# PIC18F2550_BOARD.net
KiCad netlist of a schematic drawn in EAGLE
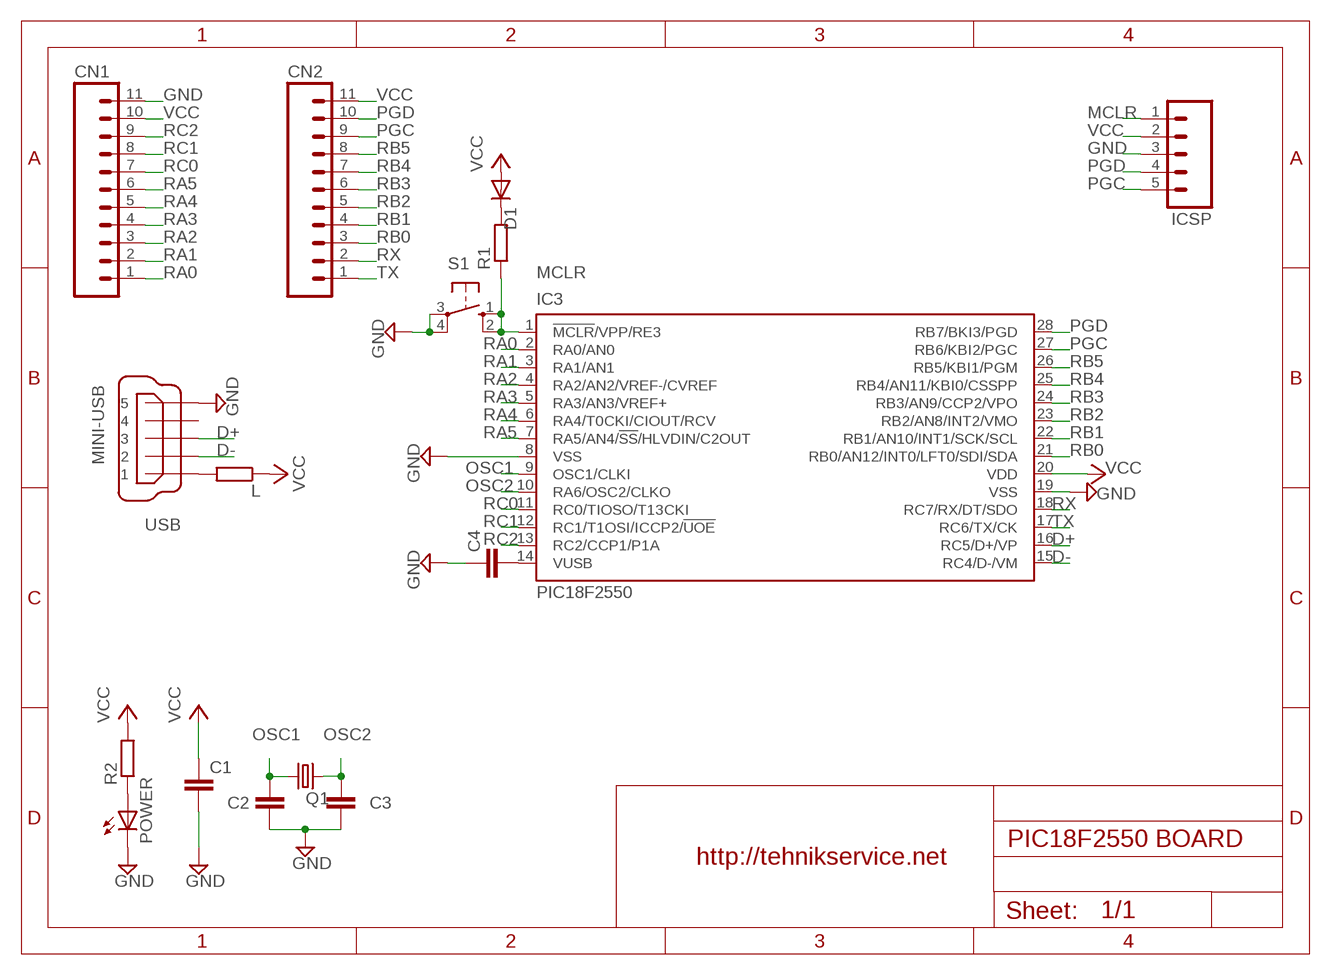
[diagram p0: schematic, sheet 1]

(export (version "E")
  (design (tool "Eeschema 10.0.6"))
  (components
    (comp (ref "C1")
      (value "C-EUC0402")
      (footprint "eagle-import:C0402")
      (libsource (lib "eagle-import") (part "C-EUC0402"))
    )
    (comp (ref "C2")
      (value "C-EUC0402")
      (footprint "eagle-import:C0402")
      (libsource (lib "eagle-import") (part "C-EUC0402"))
    )
    (comp (ref "C3")
      (value "C-EUC0402")
      (footprint "eagle-import:C0402")
      (libsource (lib "eagle-import") (part "C-EUC0402"))
    )
    (comp (ref "C4")
      (value "C-EUC0402")
      (footprint "eagle-import:C0402")
      (libsource (lib "eagle-import") (part "C-EUC0402"))
    )
    (comp (ref "CN1")
      (value "M11")
      (footprint "eagle-import:11P")
      (libsource (lib "eagle-import") (part "M11"))
    )
    (comp (ref "CN2")
      (value "M11")
      (footprint "eagle-import:11P")
      (libsource (lib "eagle-import") (part "M11"))
    )
    (comp (ref "D1")
      (value "DIODE-DO214AC")
      (footprint "eagle-import:DO214AC")
      (libsource (lib "eagle-import") (part "DIODE-DO214AC"))
    )
    (comp (ref "IC3")
      (value "PIC18F2550")
      (footprint "eagle-import:SO28W")
      (fields (field (name "MF") "MICROCHIP") (field (name "MPN") "PIC18F2550-I/SO"))
      (libsource (lib "eagle-import") (part "PIC18F2_28W550"))
    )
    (comp (ref "ICSP")
      (value "M05")
      (footprint "eagle-import:05P")
      (libsource (lib "eagle-import") (part "M05"))
    )
    (comp (ref "L")
      (value "R-EU_R0402")
      (footprint "eagle-import:R0402")
      (libsource (lib "eagle-import") (part "R-EU_R0402"))
    )
    (comp (ref "POWER")
      (value "LEDCHIP-LED0805")
      (footprint "eagle-import:CHIP-LED0805")
      (libsource (lib "eagle-import") (part "LEDCHIP-LED0805"))
    )
    (comp (ref "Q1")
      (value "CRYSTALHC49S")
      (footprint "eagle-import:HC49_S")
      (libsource (lib "eagle-import") (part "CRYSTALHC49S"))
    )
    (comp (ref "R1")
      (value "R-EU_R0402")
      (footprint "eagle-import:R0402")
      (libsource (lib "eagle-import") (part "R-EU_R0402"))
    )
    (comp (ref "R2")
      (value "R-EU_R0402")
      (footprint "eagle-import:R0402")
      (libsource (lib "eagle-import") (part "R-EU_R0402"))
    )
    (comp (ref "S1")
      (value "10-XX")
      (footprint "eagle-import:B3F-10XX")
      (fields (field (name "MPN") "B3F-1000"))
      (libsource (lib "eagle-import") (part "10-XX"))
    )
    (comp (ref "USB")
      (value "MINI-USB")
      (footprint "eagle-import:32005-201")
      (libsource (lib "eagle-import") (part "MINI-USB-32005-201"))
    )
  )
  (nets
    (net (code "1") (name "/D+") (class "Default")
      (node (ref "IC3") (pin "16") (pinfunction "RC5/D+/VP_16") (pintype "bidirectional"))
      (node (ref "USB") (pin "3") (pinfunction "3_3") (pintype "passive"))
    )
    (net (code "2") (name "/D-") (class "Default")
      (node (ref "IC3") (pin "15") (pinfunction "RC4/D-/VM_15") (pintype "bidirectional"))
      (node (ref "USB") (pin "2") (pinfunction "2_2") (pintype "passive"))
    )
    (net (code "3") (name "/MCLR") (class "Default")
      (node (ref "IC3") (pin "1") (pinfunction "~{MCLR}/VPP/RE3_1") (pintype "input"))
      (node (ref "ICSP") (pin "1") (pinfunction "1_1") (pintype "passive"))
      (node (ref "R1") (pin "1") (pinfunction "1_1") (pintype "passive"))
      (node (ref "S1") (pin "1") (pinfunction "S_1") (pintype "passive"))
      (node (ref "S1") (pin "2") (pinfunction "S1_2") (pintype "passive"))
    )
    (net (code "4") (name "/OSC1") (class "Default")
      (node (ref "C2") (pin "1") (pinfunction "1_1") (pintype "passive"))
      (node (ref "IC3") (pin "9") (pinfunction "OSC1/CLKI_9") (pintype "input"))
      (node (ref "Q1") (pin "1") (pinfunction "1_1") (pintype "passive"))
    )
    (net (code "5") (name "/OSC2") (class "Default")
      (node (ref "C3") (pin "1") (pinfunction "1_1") (pintype "passive"))
      (node (ref "IC3") (pin "10") (pinfunction "RA6/OSC2/CLKO_10") (pintype "output"))
      (node (ref "Q1") (pin "2") (pinfunction "2_2") (pintype "passive"))
    )
    (net (code "6") (name "/PGC") (class "Default")
      (node (ref "CN2") (pin "9") (pinfunction "9_9") (pintype "passive"))
      (node (ref "IC3") (pin "27") (pinfunction "RB6/KBI2/PGC_27") (pintype "bidirectional"))
      (node (ref "ICSP") (pin "5") (pinfunction "5_5") (pintype "passive"))
    )
    (net (code "7") (name "/PGD") (class "Default")
      (node (ref "CN2") (pin "10") (pinfunction "10_10") (pintype "passive"))
      (node (ref "IC3") (pin "28") (pinfunction "RB7/BKI3/PGD_28") (pintype "bidirectional"))
      (node (ref "ICSP") (pin "4") (pinfunction "4_4") (pintype "passive"))
    )
    (net (code "8") (name "/RA0") (class "Default")
      (node (ref "CN1") (pin "1") (pinfunction "1_1") (pintype "passive"))
      (node (ref "IC3") (pin "2") (pinfunction "RA0/AN0_2") (pintype "bidirectional"))
    )
    (net (code "9") (name "/RA1") (class "Default")
      (node (ref "CN1") (pin "2") (pinfunction "2_2") (pintype "passive"))
      (node (ref "IC3") (pin "3") (pinfunction "RA1/AN1_3") (pintype "bidirectional"))
    )
    (net (code "10") (name "/RA2") (class "Default")
      (node (ref "CN1") (pin "3") (pinfunction "3_3") (pintype "passive"))
      (node (ref "IC3") (pin "4") (pinfunction "RA2/AN2/VREF-/CVREF_4") (pintype "bidirectional"))
    )
    (net (code "11") (name "/RA3") (class "Default")
      (node (ref "CN1") (pin "4") (pinfunction "4_4") (pintype "passive"))
      (node (ref "IC3") (pin "5") (pinfunction "RA3/AN3/VREF+_5") (pintype "bidirectional"))
    )
    (net (code "12") (name "/RA4") (class "Default")
      (node (ref "CN1") (pin "5") (pinfunction "5_5") (pintype "passive"))
      (node (ref "IC3") (pin "6") (pinfunction "RA4/T0CKI/CIOUT/RCV_6") (pintype "bidirectional"))
    )
    (net (code "13") (name "/RA5") (class "Default")
      (node (ref "CN1") (pin "6") (pinfunction "6_6") (pintype "passive"))
      (node (ref "IC3") (pin "7") (pinfunction "RA5/AN4/~{SS}/HLVDIN/C2OUT_7") (pintype "bidirectional"))
    )
    (net (code "14") (name "/RB0") (class "Default")
      (node (ref "CN2") (pin "3") (pinfunction "3_3") (pintype "passive"))
      (node (ref "IC3") (pin "21") (pinfunction "RB0/AN12/INT0/LFT0/SDI/SDA_21") (pintype "bidirectional"))
    )
    (net (code "15") (name "/RB1") (class "Default")
      (node (ref "CN2") (pin "4") (pinfunction "4_4") (pintype "passive"))
      (node (ref "IC3") (pin "22") (pinfunction "RB1/AN10/INT1/SCK/SCL_22") (pintype "bidirectional"))
    )
    (net (code "16") (name "/RB2") (class "Default")
      (node (ref "CN2") (pin "5") (pinfunction "5_5") (pintype "passive"))
      (node (ref "IC3") (pin "23") (pinfunction "RB2/AN8/INT2/VMO_23") (pintype "bidirectional"))
    )
    (net (code "17") (name "/RB3") (class "Default")
      (node (ref "CN2") (pin "6") (pinfunction "6_6") (pintype "passive"))
      (node (ref "IC3") (pin "24") (pinfunction "RB3/AN9/CCP2/VPO_24") (pintype "bidirectional"))
    )
    (net (code "18") (name "/RB4") (class "Default")
      (node (ref "CN2") (pin "7") (pinfunction "7_7") (pintype "passive"))
      (node (ref "IC3") (pin "25") (pinfunction "RB4/AN11/KBI0/CSSPP_25") (pintype "bidirectional"))
    )
    (net (code "19") (name "/RB5") (class "Default")
      (node (ref "CN2") (pin "8") (pinfunction "8_8") (pintype "passive"))
      (node (ref "IC3") (pin "26") (pinfunction "RB5/KBI1/PGM_26") (pintype "bidirectional"))
    )
    (net (code "20") (name "/RC0") (class "Default")
      (node (ref "CN1") (pin "7") (pinfunction "7_7") (pintype "passive"))
      (node (ref "IC3") (pin "11") (pinfunction "RC0/TIOSO/T13CKI_11") (pintype "bidirectional"))
    )
    (net (code "21") (name "/RC1") (class "Default")
      (node (ref "CN1") (pin "8") (pinfunction "8_8") (pintype "passive"))
      (node (ref "IC3") (pin "12") (pinfunction "RC1/T1OSI/ICCP2/~{UOE}_12") (pintype "bidirectional"))
    )
    (net (code "22") (name "/RC2") (class "Default")
      (node (ref "CN1") (pin "9") (pinfunction "9_9") (pintype "passive"))
      (node (ref "IC3") (pin "13") (pinfunction "RC2/CCP1/P1A_13") (pintype "bidirectional"))
    )
    (net (code "23") (name "/RX") (class "Default")
      (node (ref "CN2") (pin "2") (pinfunction "2_2") (pintype "passive"))
      (node (ref "IC3") (pin "18") (pinfunction "RC7/RX/DT/SDO_18") (pintype "bidirectional"))
    )
    (net (code "24") (name "/TX") (class "Default")
      (node (ref "CN2") (pin "1") (pinfunction "1_1") (pintype "passive"))
      (node (ref "IC3") (pin "17") (pinfunction "RC6/TX/CK_17") (pintype "bidirectional"))
    )
    (net (code "25") (name "GND") (class "Default")
      (node (ref "C1") (pin "2") (pinfunction "2_2") (pintype "passive"))
      (node (ref "C2") (pin "2") (pinfunction "2_2") (pintype "passive"))
      (node (ref "C3") (pin "2") (pinfunction "2_2") (pintype "passive"))
      (node (ref "C4") (pin "1") (pinfunction "1_1") (pintype "passive"))
      (node (ref "CN1") (pin "11") (pinfunction "11_11") (pintype "passive"))
      (node (ref "IC3") (pin "19") (pinfunction "VSS_19") (pintype "power_in"))
      (node (ref "IC3") (pin "8") (pinfunction "VSS_8") (pintype "power_in"))
      (node (ref "ICSP") (pin "3") (pinfunction "3_3") (pintype "passive"))
      (node (ref "POWER") (pin "C") (pinfunction "C_C") (pintype "passive"))
      (node (ref "S1") (pin "3") (pinfunction "P_3") (pintype "passive"))
      (node (ref "S1") (pin "4") (pinfunction "P1_4") (pintype "passive"))
      (node (ref "USB") (pin "5") (pinfunction "5_5") (pintype "passive"))
    )
    (net (code "26") (name "Net-(D1-PadC)") (class "Default")
      (node (ref "D1") (pin "C") (pinfunction "C_C") (pintype "passive"))
      (node (ref "R1") (pin "2") (pinfunction "2_2") (pintype "passive"))
    )
    (net (code "27") (name "Net-(IC3-VUSB)") (class "Default")
      (node (ref "C4") (pin "2") (pinfunction "2_2") (pintype "passive"))
      (node (ref "IC3") (pin "14") (pinfunction "VUSB_14") (pintype "bidirectional"))
    )
    (net (code "28") (name "Net-(L-Pad2)") (class "Default")
      (node (ref "L") (pin "2") (pinfunction "2_2") (pintype "passive"))
      (node (ref "USB") (pin "1") (pinfunction "1_1") (pintype "passive"))
    )
    (net (code "29") (name "Net-(POWER-PadA)") (class "Default")
      (node (ref "POWER") (pin "A") (pinfunction "A_A") (pintype "passive"))
      (node (ref "R2") (pin "1") (pinfunction "1_1") (pintype "passive"))
    )
    (net (code "30") (name "VCC") (class "Default")
      (node (ref "C1") (pin "1") (pinfunction "1_1") (pintype "passive"))
      (node (ref "CN1") (pin "10") (pinfunction "10_10") (pintype "passive"))
      (node (ref "CN2") (pin "11") (pinfunction "11_11") (pintype "passive"))
      (node (ref "D1") (pin "A") (pinfunction "A_A") (pintype "passive"))
      (node (ref "IC3") (pin "20") (pinfunction "VDD_20") (pintype "power_in"))
      (node (ref "ICSP") (pin "2") (pinfunction "2_2") (pintype "passive"))
      (node (ref "L") (pin "1") (pinfunction "1_1") (pintype "passive"))
      (node (ref "R2") (pin "2") (pinfunction "2_2") (pintype "passive"))
    )
    (net (code "31") (name "unconnected-(USB-Pad4)") (class "Default")
      (node (ref "USB") (pin "4") (pinfunction "4_4") (pintype "passive"))
    )
  )
)
